# ecg_module_v2_0_1_jan2024.net
KiCad netlist of a schematic drawn in EAGLE
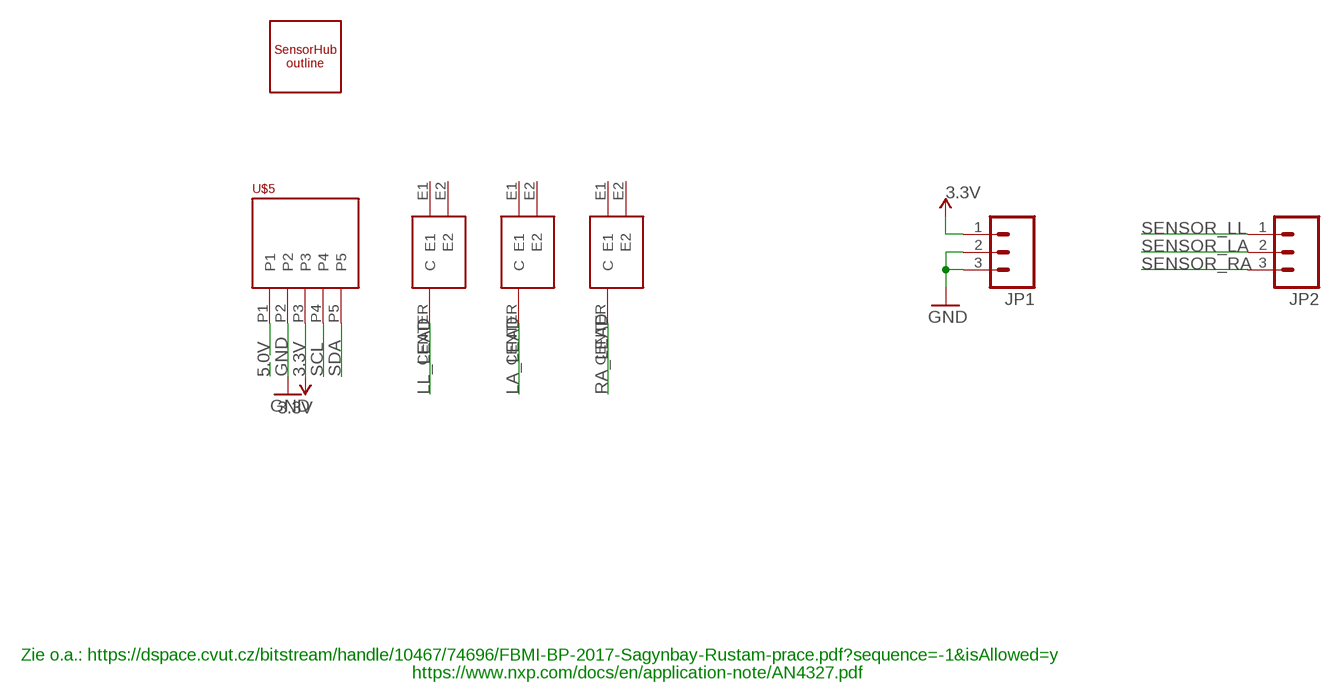
[diagram p0: schematic, sheet 1]
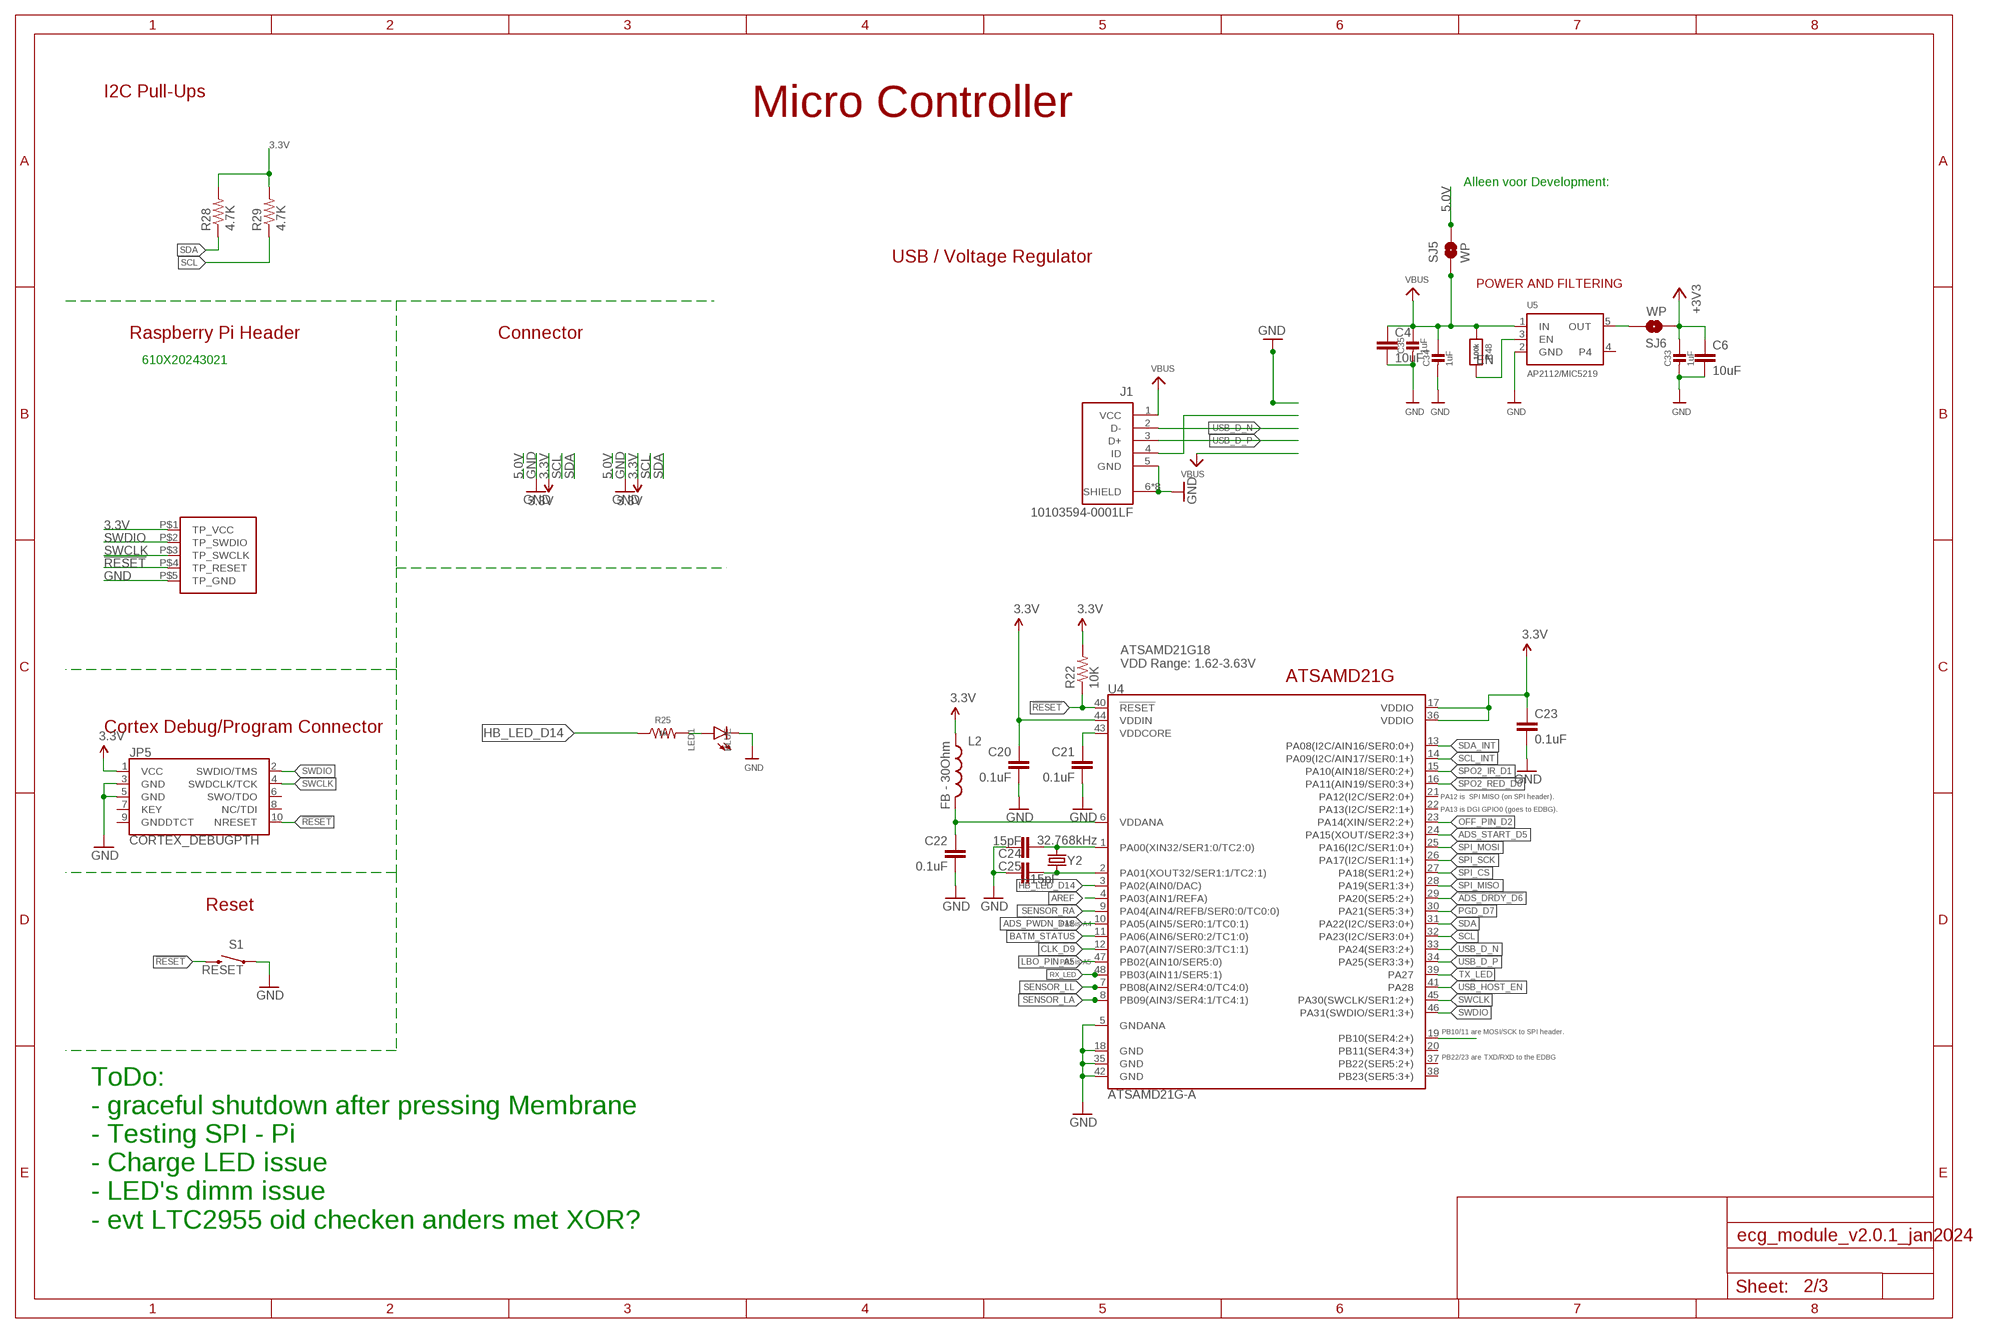
[diagram p1: schematic, sheet 2]
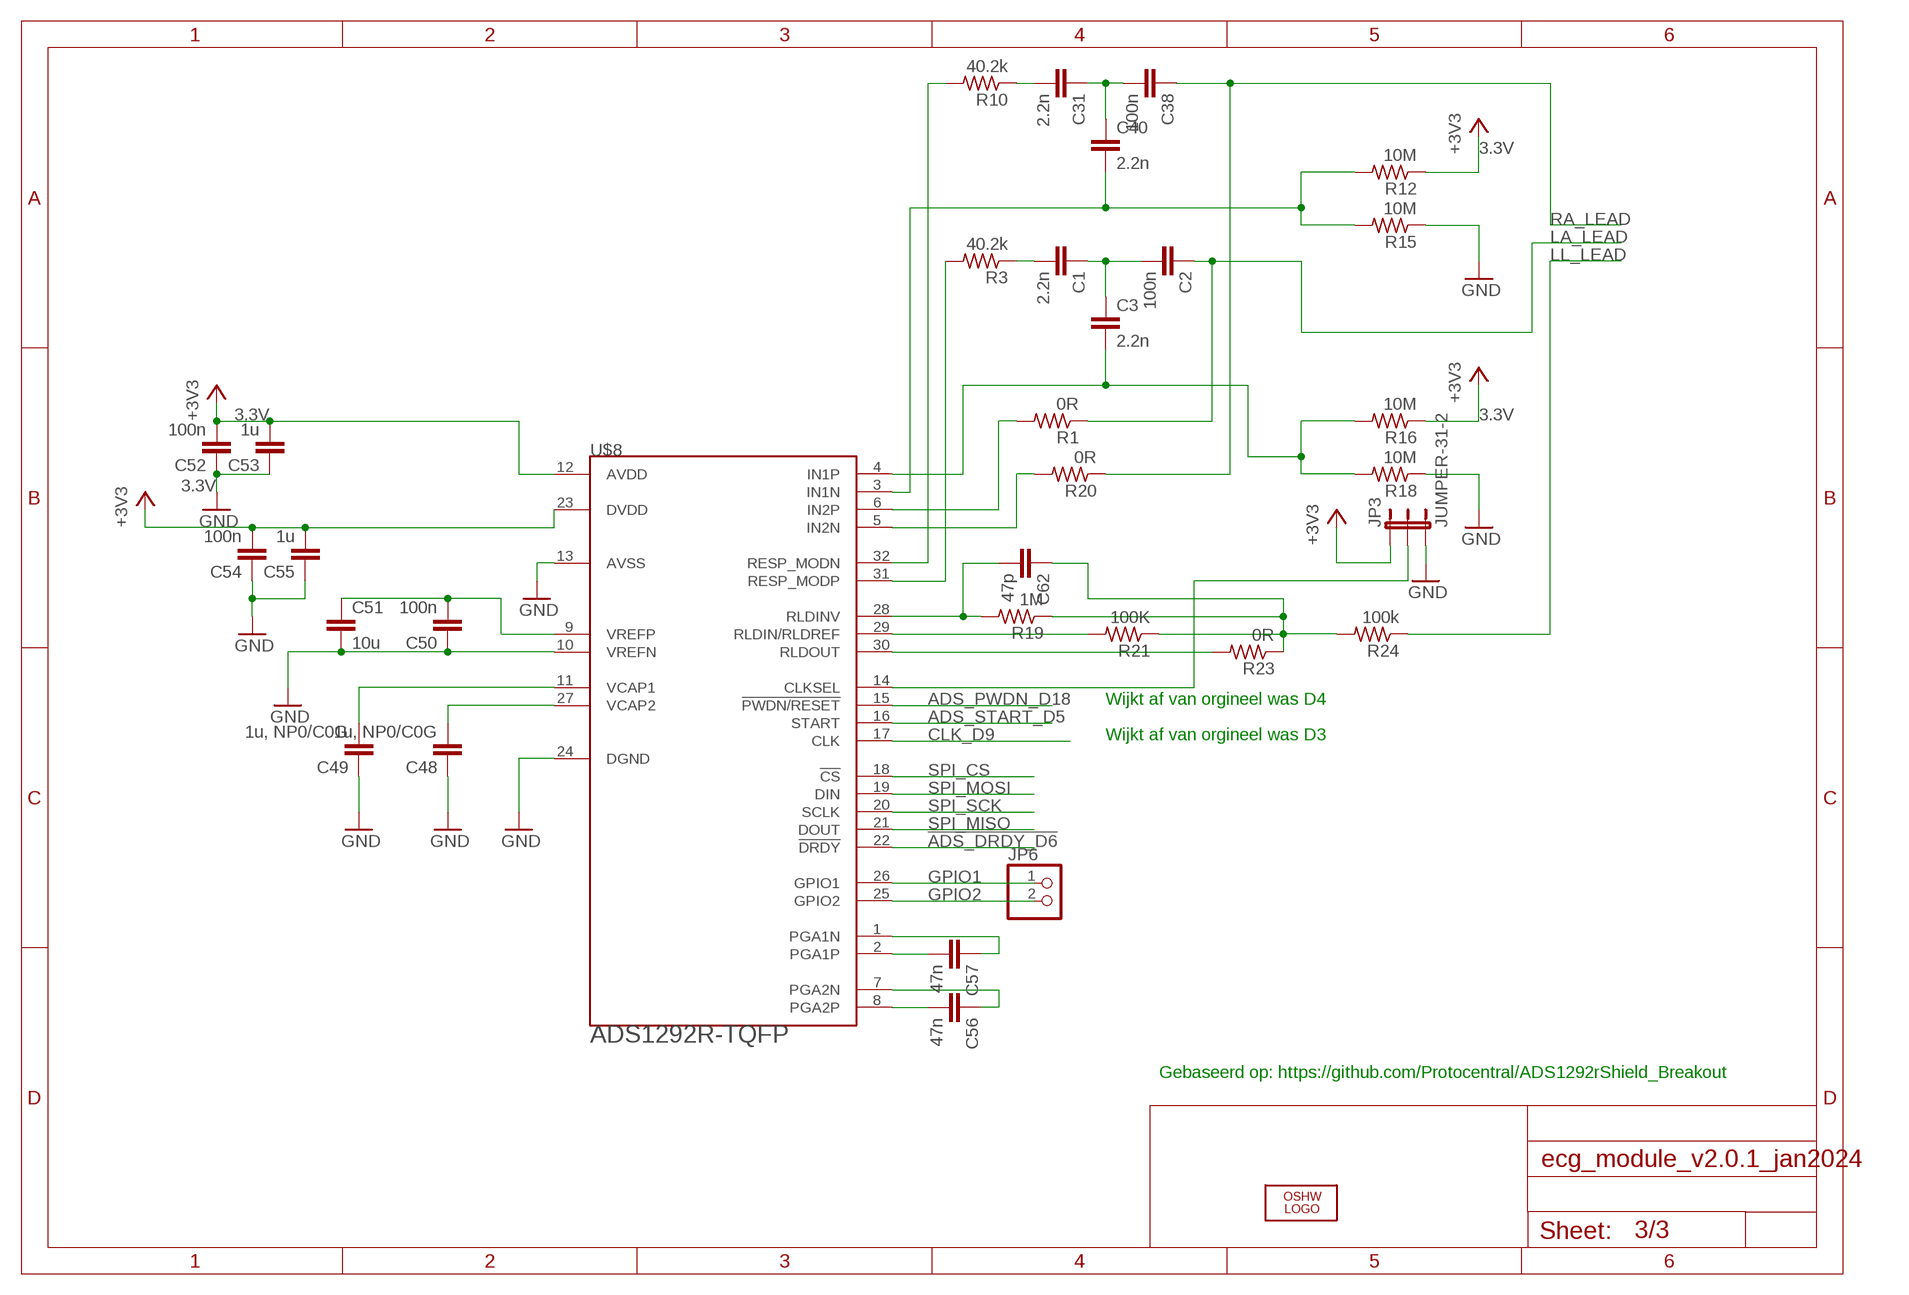
[diagram p2: schematic, sheet 3]

(export (version "E")
  (design (tool "Eeschema 10.0.6"))
  (components
    (comp (ref "C1")
      (value "2.2n")
      (footprint "eagle-import:C0402")
      (libsource (lib "eagle-import") (part "C-EUC0402"))
    )
    (comp (ref "C2")
      (value "100n")
      (footprint "eagle-import:C0402")
      (libsource (lib "eagle-import") (part "C-EUC0402"))
    )
    (comp (ref "C3")
      (value "2.2n")
      (footprint "eagle-import:C0402")
      (libsource (lib "eagle-import") (part "C-EUC0402"))
    )
    (comp (ref "C31")
      (value "2.2n")
      (footprint "eagle-import:C0402")
      (libsource (lib "eagle-import") (part "C-EUC0402"))
    )
    (comp (ref "C38")
      (value "100n")
      (footprint "eagle-import:C0402")
      (libsource (lib "eagle-import") (part "C-EUC0402"))
    )
    (comp (ref "C40")
      (value "2.2n")
      (footprint "eagle-import:C0402")
      (libsource (lib "eagle-import") (part "C-EUC0402"))
    )
    (comp (ref "C48")
      (value "1u, NP0/C0G")
      (footprint "eagle-import:C0402")
      (libsource (lib "eagle-import") (part "C-EUC0402"))
    )
    (comp (ref "C49")
      (value "1u, NP0/C0G")
      (footprint "eagle-import:C0402")
      (libsource (lib "eagle-import") (part "C-EUC0402"))
    )
    (comp (ref "C50")
      (value "100n")
      (footprint "eagle-import:C0402")
      (libsource (lib "eagle-import") (part "C-EUC0402"))
    )
    (comp (ref "C51")
      (value "10u")
      (footprint "eagle-import:C0603")
      (libsource (lib "eagle-import") (part "resistor_348_C-EUC0603"))
    )
    (comp (ref "C52")
      (value "100n")
      (footprint "eagle-import:C0402")
      (libsource (lib "eagle-import") (part "C-EUC0402"))
    )
    (comp (ref "C53")
      (value "1u")
      (footprint "eagle-import:C0402")
      (libsource (lib "eagle-import") (part "C-EUC0402"))
    )
    (comp (ref "C54")
      (value "100n")
      (footprint "eagle-import:C0402")
      (libsource (lib "eagle-import") (part "C-EUC0402"))
    )
    (comp (ref "C55")
      (value "1u")
      (footprint "eagle-import:C0402")
      (libsource (lib "eagle-import") (part "C-EUC0402"))
    )
    (comp (ref "C56")
      (value "47n")
      (footprint "eagle-import:C0402")
      (libsource (lib "eagle-import") (part "C-EUC0402"))
    )
    (comp (ref "C57")
      (value "47n")
      (footprint "eagle-import:C0402")
      (libsource (lib "eagle-import") (part "C-EUC0402"))
    )
    (comp (ref "C62")
      (value "47p")
      (footprint "eagle-import:C0402")
      (libsource (lib "eagle-import") (part "C-EUC0402"))
    )
    (comp (ref "JP3")
      (value "JUMPER-31-2")
      (footprint "eagle-import:SJ_3_PASTE1&2")
      (libsource (lib "eagle-import") (part "JUMPER-31-2"))
    )
    (comp (ref "JP6")
      (value "PINHD-1X2")
      (footprint "eagle-import:1X02")
      (libsource (lib "eagle-import") (part "PINHD-1X2"))
    )
    (comp (ref "LOGO1")
      (value "OSHW_LOGO_FILLX0100-NT")
      (footprint "eagle-import:OSHW_FILLX100_NOTEXT")
      (libsource (lib "eagle-import") (part "OSHW_LOGO_FILLX0100-NT"))
    )
    (comp (ref "R1")
      (value "0R")
      (footprint "eagle-import:R0402")
      (libsource (lib "eagle-import") (part "R-US_R0402"))
    )
    (comp (ref "R3")
      (value "40.2k")
      (footprint "eagle-import:R0402")
      (libsource (lib "eagle-import") (part "R-US_R0402"))
    )
    (comp (ref "R10")
      (value "40.2k")
      (footprint "eagle-import:R0402")
      (libsource (lib "eagle-import") (part "R-US_R0402"))
    )
    (comp (ref "R12")
      (value "10M")
      (footprint "eagle-import:R0402")
      (libsource (lib "eagle-import") (part "R-US_R0402"))
    )
    (comp (ref "R15")
      (value "10M")
      (footprint "eagle-import:R0402")
      (libsource (lib "eagle-import") (part "R-US_R0402"))
    )
    (comp (ref "R16")
      (value "10M")
      (footprint "eagle-import:R0402")
      (libsource (lib "eagle-import") (part "R-US_R0402"))
    )
    (comp (ref "R18")
      (value "10M")
      (footprint "eagle-import:R0402")
      (libsource (lib "eagle-import") (part "R-US_R0402"))
    )
    (comp (ref "R19")
      (value "1M")
      (footprint "eagle-import:R0402")
      (libsource (lib "eagle-import") (part "R-US_R0402"))
    )
    (comp (ref "R20")
      (value "0R")
      (footprint "eagle-import:R0402")
      (libsource (lib "eagle-import") (part "R-US_R0402"))
    )
    (comp (ref "R21")
      (value "100K")
      (footprint "eagle-import:R0402")
      (libsource (lib "eagle-import") (part "R-US_R0402"))
    )
    (comp (ref "R23")
      (value "0R")
      (footprint "eagle-import:R0402")
      (libsource (lib "eagle-import") (part "R-US_R0402"))
    )
    (comp (ref "R24")
      (value "100k")
      (footprint "eagle-import:R0402")
      (libsource (lib "eagle-import") (part "R-US_R0402"))
    )
    (comp (ref "U$8")
      (value "ADS1292R-TQFP")
      (footprint "eagle-import:SQFP-S-5X5-32")
      (libsource (lib "eagle-import") (part "ADS1292R-TQFP"))
    )
    (comp (ref "C4")
      (value "10uF")
      (footprint "eagle-import:0603")
      (libsource (lib "eagle-import") (part "10UF-0603-6.3V-20%"))
    )
    (comp (ref "C6")
      (value "10uF")
      (footprint "eagle-import:0603")
      (libsource (lib "eagle-import") (part "10UF-0603-6.3V-20%"))
    )
    (comp (ref "C20")
      (value "0.1uF")
      (footprint "eagle-import:0402-CAP")
      (libsource (lib "eagle-import") (part "0.1UF-16V(+-10%)(0402)"))
    )
    (comp (ref "C21")
      (value "0.1uF")
      (footprint "eagle-import:0603")
      (libsource (lib "eagle-import") (part "0.1UF-0603-25V-(+80/-20%)"))
    )
    (comp (ref "C22")
      (value "0.1uF")
      (footprint "eagle-import:0402-CAP")
      (libsource (lib "eagle-import") (part "0.1UF-16V(+-10%)(0402)"))
    )
    (comp (ref "C23")
      (value "0.1uF")
      (footprint "eagle-import:0402-CAP")
      (libsource (lib "eagle-import") (part "0.1UF-16V(+-10%)(0402)"))
    )
    (comp (ref "C24")
      (value "15pF")
      (footprint "eagle-import:0402-CAP")
      (libsource (lib "eagle-import") (part "15PF-50V(+-5%)(0402)"))
    )
    (comp (ref "C25")
      (value "15pF")
      (footprint "eagle-import:0402-CAP")
      (libsource (lib "eagle-import") (part "15PF-50V(+-5%)(0402)"))
    )
    (comp (ref "C33")
      (value "1uF")
      (footprint "eagle-import:0603-NO")
      (libsource (lib "eagle-import") (part "CAP_CERAMIC0603_NO"))
    )
    (comp (ref "C34")
      (value "1uF")
      (footprint "eagle-import:0603-NO")
      (libsource (lib "eagle-import") (part "CAP_CERAMIC0603_NO"))
    )
    (comp (ref "C35")
      (value "1uF")
      (footprint "eagle-import:0603-NO")
      (libsource (lib "eagle-import") (part "CAP_CERAMIC0603_NO"))
    )
    (comp (ref "J1")
      (value "10103594-0001LF")
      (footprint "eagle-import:AMPHENOL_10103594-0001LF")
      (fields (field (name "MF") "AMPHENOL ICC / FCI"))
      (libsource (lib "eagle-import") (part "10103594-0001LF"))
    )
    (comp (ref "JP5")
      (value "CORTEX_DEBUGPTH")
      (footprint "eagle-import:2X5-PTH-1.27MM")
      (libsource (lib "eagle-import") (part "CORTEX_DEBUGPTH"))
    )
    (comp (ref "L2")
      (value "FB - 30Ohm")
      (footprint "eagle-import:0603")
      (libsource (lib "eagle-import") (part "INDUCTOR0603"))
    )
    (comp (ref "LED1")
      (value "BLUE")
      (footprint "eagle-import:CHIP-LED0603")
      (libsource (lib "eagle-import") (part "LEDCHIP-LED0603"))
    )
    (comp (ref "R22")
      (value "10K")
      (footprint "eagle-import:0603-RES")
      (libsource (lib "eagle-import") (part "10KOHM-1/10W-1%(0603)0603"))
    )
    (comp (ref "R25")
      (value "1k")
      (footprint "eagle-import:0603")
      (libsource (lib "eagle-import") (part "1KOHM-0603-1/10W-1%"))
    )
    (comp (ref "R28")
      (value "4.7K")
      (footprint "eagle-import:0603-RES")
      (libsource (lib "eagle-import") (part "4.7KOHM-1/10W-1%(0603)"))
    )
    (comp (ref "R29")
      (value "4.7K")
      (footprint "eagle-import:0603-RES")
      (libsource (lib "eagle-import") (part "4.7KOHM-1/10W-1%(0603)"))
    )
    (comp (ref "R48")
      (value "100k")
      (footprint "eagle-import:0603-NO@1")
      (libsource (lib "eagle-import") (part "RESISTOR_0603_NOOUT"))
    )
    (comp (ref "S1")
      (value "RESET")
      (footprint "eagle-import:TACTILE_SWITCH_SMD_4.6X2.8MM")
      (libsource (lib "eagle-import") (part "SWITCH-MOMENTARY-2SMD-4.6X2.8MM"))
    )
    (comp (ref "SJ5")
      (value "WP")
      (footprint "eagle-import:SMT-JUMPER_2_NO_NO-SILK")
      (libsource (lib "eagle-import") (part "JUMPER-SMT_2_NO_NO-SILK"))
    )
    (comp (ref "SJ6")
      (value "WP")
      (footprint "eagle-import:SMT-JUMPER_2_NO_NO-SILK")
      (libsource (lib "eagle-import") (part "JUMPER-SMT_2_NO_NO-SILK"))
    )
    (comp (ref "U$9")
      (value "HUB_TESTPINSHUBS")
      (footprint "eagle-import:TEST_PINS")
      (libsource (lib "eagle-import") (part "HUB_TESTPINSHUBS"))
    )
    (comp (ref "U4")
      (value "ATSAMD21G-A")
      (footprint "eagle-import:TQFP-48")
      (libsource (lib "eagle-import") (part "ATSAMD21G-A"))
    )
    (comp (ref "U5")
      (value "AP2112/MIC5219")
      (footprint "eagle-import:SOT23-5")
      (libsource (lib "eagle-import") (part "VREG_SOT23-5"))
    )
    (comp (ref "Y2")
      (value "32.768kHz")
      (footprint "eagle-import:CRYSTAL-SMD-3.2X1.5MM")
      (libsource (lib "eagle-import") (part "CRYSTAL3.2X1.5MM"))
    )
    (comp (ref "JP1")
      (value "M03PTH")
      (footprint "eagle-import:1X03")
      (libsource (lib "eagle-import") (part "M03PTH"))
    )
    (comp (ref "JP2")
      (value "M03PTH")
      (footprint "eagle-import:1X03")
      (libsource (lib "eagle-import") (part "M03PTH"))
    )
    (comp (ref "U$1")
      (value "DIN_ECG_EEG")
      (footprint "eagle-import:EEG_ECG_DIN")
      (libsource (lib "eagle-import") (part "DIN_ECG_EEG"))
    )
    (comp (ref "U$3")
      (value "DIN_ECG_EEG")
      (footprint "eagle-import:EEG_ECG_DIN")
      (libsource (lib "eagle-import") (part "DIN_ECG_EEG"))
    )
    (comp (ref "U$4")
      (value "DIN_ECG_EEG")
      (footprint "eagle-import:EEG_ECG_DIN")
      (libsource (lib "eagle-import") (part "DIN_ECG_EEG"))
    )
    (comp (ref "U$5")
      (value "PHOENIX_PTSM_M5_TH_I2C++")
      (footprint "eagle-import:PTSM_M5_THRHOLE")
      (libsource (lib "eagle-import") (part "PHOENIX_PTSM_M5_TH_I2C++"))
    )
    (comp (ref "U$12")
      (value "SENSORHUB_PROFILEUSB_LEFT")
      (footprint "eagle-import:SENSORHUB_OUTLINE_USB_NOTCH_LEFT")
      (libsource (lib "eagle-import") (part "SENSORHUB_PROFILEUSB_LEFT"))
    )
  )
  (nets
    (net (code "1") (name "3.3V") (class "Default")
      (node (ref "C20") (pin "1") (pinfunction "1_1") (pintype "passive"))
      (node (ref "C23") (pin "1") (pinfunction "1_1") (pintype "passive"))
      (node (ref "C33") (pin "1") (pinfunction "1_1") (pintype "passive"))
      (node (ref "C52") (pin "2") (pinfunction "2_2") (pintype "passive"))
      (node (ref "C53") (pin "2") (pinfunction "2_2") (pintype "passive"))
      (node (ref "C54") (pin "2") (pinfunction "2_2") (pintype "passive"))
      (node (ref "C55") (pin "2") (pinfunction "2_2") (pintype "passive"))
      (node (ref "C6") (pin "1") (pinfunction "1_1") (pintype "passive"))
      (node (ref "JP1") (pin "1") (pinfunction "1_1") (pintype "passive"))
      (node (ref "JP3") (pin "1") (pinfunction "1_1") (pintype "passive"))
      (node (ref "JP5") (pin "1") (pinfunction "VCC_1") (pintype "bidirectional"))
      (node (ref "L2") (pin "1") (pinfunction "1_1") (pintype "passive"))
      (node (ref "R12") (pin "1") (pinfunction "1_1") (pintype "passive"))
      (node (ref "R16") (pin "1") (pinfunction "1_1") (pintype "passive"))
      (node (ref "R22") (pin "2") (pinfunction "2_2") (pintype "passive"))
      (node (ref "R28") (pin "2") (pinfunction "2_2") (pintype "passive"))
      (node (ref "R29") (pin "2") (pinfunction "2_2") (pintype "passive"))
      (node (ref "SJ6") (pin "1") (pinfunction "1_1") (pintype "passive"))
      (node (ref "U$5") (pin "P3") (pinfunction "P3_P3") (pintype "power_in"))
      (node (ref "U$8") (pin "12") (pinfunction "AVDD_12") (pintype "power_in"))
      (node (ref "U$8") (pin "23") (pinfunction "DVDD_23") (pintype "power_in"))
      (node (ref "U$9") (pin "P$1") (pinfunction "TP_VCC_P$1") (pintype "bidirectional"))
      (node (ref "U4") (pin "17") (pinfunction "VDDIO_17") (pintype "bidirectional"))
      (node (ref "U4") (pin "36") (pinfunction "VDDIO_36") (pintype "bidirectional"))
      (node (ref "U4") (pin "44") (pinfunction "VDDIN_44") (pintype "bidirectional"))
    )
    (net (code "2") (name "5.0V") (class "Default")
      (node (ref "SJ5") (pin "2") (pinfunction "2_2") (pintype "passive"))
      (node (ref "U$5") (pin "P1") (pinfunction "P1_P1") (pintype "power_in"))
    )
    (net (code "3") (name "ADS_PWDN_D18") (class "Default")
      (node (ref "U$8") (pin "15") (pinfunction "~{PWDN/RESET}_15") (pintype "bidirectional"))
      (node (ref "U4") (pin "10") (pinfunction "PA05(AIN5/SER0:1/TC0:1)_10") (pintype "bidirectional"))
    )
    (net (code "4") (name "ADS_START_D5") (class "Default")
      (node (ref "U$8") (pin "16") (pinfunction "START_16") (pintype "bidirectional"))
      (node (ref "U4") (pin "24") (pinfunction "PA15(XOUT/SER2:3+)_24") (pintype "bidirectional"))
    )
    (net (code "5") (name "AREF") (class "Default")
      (node (ref "U4") (pin "4") (pinfunction "PA03(AIN1/REFA)_4") (pintype "bidirectional"))
    )
    (net (code "6") (name "BATM_STATUS") (class "Default")
      (node (ref "U4") (pin "11") (pinfunction "PA06(AIN6/SER0:2/TC1:0)_11") (pintype "bidirectional"))
    )
    (net (code "7") (name "CLK_D9") (class "Default")
      (node (ref "U$8") (pin "17") (pinfunction "CLK_17") (pintype "bidirectional"))
      (node (ref "U4") (pin "12") (pinfunction "PA07(AIN7/SER0:3/TC1:1)_12") (pintype "bidirectional"))
    )
    (net (code "8") (name "EN") (class "Default")
      (node (ref "R48") (pin "2") (pinfunction "2_2") (pintype "passive"))
      (node (ref "U5") (pin "3") (pinfunction "EN_3") (pintype "input"))
    )
    (net (code "9") (name "GND") (class "Default")
      (node (ref "C20") (pin "2") (pinfunction "2_2") (pintype "passive"))
      (node (ref "C21") (pin "2") (pinfunction "2_2") (pintype "passive"))
      (node (ref "C22") (pin "2") (pinfunction "2_2") (pintype "passive"))
      (node (ref "C23") (pin "2") (pinfunction "2_2") (pintype "passive"))
      (node (ref "C24") (pin "1") (pinfunction "1_1") (pintype "passive"))
      (node (ref "C25") (pin "2") (pinfunction "2_2") (pintype "passive"))
      (node (ref "C33") (pin "2") (pinfunction "2_2") (pintype "passive"))
      (node (ref "C34") (pin "2") (pinfunction "2_2") (pintype "passive"))
      (node (ref "C35") (pin "2") (pinfunction "2_2") (pintype "passive"))
      (node (ref "C4") (pin "2") (pinfunction "2_2") (pintype "passive"))
      (node (ref "C48") (pin "1") (pinfunction "1_1") (pintype "passive"))
      (node (ref "C49") (pin "1") (pinfunction "1_1") (pintype "passive"))
      (node (ref "C50") (pin "1") (pinfunction "1_1") (pintype "passive"))
      (node (ref "C51") (pin "2") (pinfunction "2_2") (pintype "passive"))
      (node (ref "C52") (pin "1") (pinfunction "1_1") (pintype "passive"))
      (node (ref "C53") (pin "1") (pinfunction "1_1") (pintype "passive"))
      (node (ref "C54") (pin "1") (pinfunction "1_1") (pintype "passive"))
      (node (ref "C55") (pin "1") (pinfunction "1_1") (pintype "passive"))
      (node (ref "C6") (pin "2") (pinfunction "2_2") (pintype "passive"))
      (node (ref "J1") (pin "10") (pinfunction "SHIELD_10") (pintype "passive"))
      (node (ref "J1") (pin "11") (pinfunction "SHIELD_11") (pintype "passive"))
      (node (ref "J1") (pin "5") (pinfunction "GND_5") (pintype "power_in"))
      (node (ref "J1") (pin "6") (pinfunction "SHIELD_6") (pintype "passive"))
      (node (ref "J1") (pin "7") (pinfunction "SHIELD_7") (pintype "passive"))
      (node (ref "J1") (pin "8") (pinfunction "SHIELD_8") (pintype "passive"))
      (node (ref "J1") (pin "9") (pinfunction "SHIELD_9") (pintype "passive"))
      (node (ref "J1") (pin "S1") (pinfunction "SHIELD_S1") (pintype "passive"))
      (node (ref "J1") (pin "S2") (pinfunction "SHIELD_S2") (pintype "passive"))
      (node (ref "JP1") (pin "2") (pinfunction "2_2") (pintype "passive"))
      (node (ref "JP1") (pin "3") (pinfunction "3_3") (pintype "passive"))
      (node (ref "JP3") (pin "3") (pinfunction "3_3") (pintype "passive"))
      (node (ref "JP5") (pin "3") (pinfunction "GND_3") (pintype "bidirectional"))
      (node (ref "JP5") (pin "5") (pinfunction "GND_5") (pintype "bidirectional"))
      (node (ref "LED1") (pin "C") (pinfunction "C_C") (pintype "passive"))
      (node (ref "R15") (pin "1") (pinfunction "1_1") (pintype "passive"))
      (node (ref "R18") (pin "1") (pinfunction "1_1") (pintype "passive"))
      (node (ref "S1") (pin "1") (pinfunction "1_1") (pintype "passive"))
      (node (ref "S1") (pin "2") (pinfunction "1_2") (pintype "passive"))
      (node (ref "U$5") (pin "P2") (pinfunction "P2_P2") (pintype "power_in"))
      (node (ref "U$8") (pin "10") (pinfunction "VREFN_10") (pintype "bidirectional"))
      (node (ref "U$8") (pin "13") (pinfunction "AVSS_13") (pintype "bidirectional"))
      (node (ref "U$8") (pin "24") (pinfunction "DGND_24") (pintype "bidirectional"))
      (node (ref "U$9") (pin "P$5") (pinfunction "TP_GND_P$5") (pintype "bidirectional"))
      (node (ref "U4") (pin "18") (pinfunction "GND_18") (pintype "bidirectional"))
      (node (ref "U4") (pin "35") (pinfunction "GND_35") (pintype "bidirectional"))
      (node (ref "U4") (pin "42") (pinfunction "GND_42") (pintype "bidirectional"))
      (node (ref "U4") (pin "5") (pinfunction "GNDANA_5") (pintype "bidirectional"))
      (node (ref "U5") (pin "2") (pinfunction "GND_2") (pintype "power_in"))
    )
    (net (code "10") (name "GPIO1") (class "Default")
      (node (ref "JP6") (pin "1") (pinfunction "1_1") (pintype "passive"))
      (node (ref "U$8") (pin "26") (pinfunction "GPIO1_26") (pintype "bidirectional"))
    )
    (net (code "11") (name "GPIO2") (class "Default")
      (node (ref "JP6") (pin "2") (pinfunction "2_2") (pintype "passive"))
      (node (ref "U$8") (pin "25") (pinfunction "GPIO2_25") (pintype "bidirectional"))
    )
    (net (code "12") (name "HB_LED_D14") (class "Default")
      (node (ref "R25") (pin "1") (pinfunction "1_1") (pintype "passive"))
      (node (ref "U4") (pin "3") (pinfunction "PA02(AIN0/DAC)_3") (pintype "bidirectional"))
    )
    (net (code "13") (name "LA_LEAD") (class "Default")
      (node (ref "C2") (pin "1") (pinfunction "1_1") (pintype "passive"))
      (node (ref "R1") (pin "1") (pinfunction "1_1") (pintype "passive"))
      (node (ref "U$3") (pin "CENTER") (pinfunction "C_CENTER") (pintype "bidirectional"))
    )
    (net (code "14") (name "LBO_PIN_A5") (class "Default")
      (node (ref "U4") (pin "47") (pinfunction "PB02(AIN10/SER5:0)_47") (pintype "bidirectional"))
    )
    (net (code "15") (name "LL_LEAD") (class "Default")
      (node (ref "R24") (pin "1") (pinfunction "1_1") (pintype "passive"))
      (node (ref "U$1") (pin "CENTER") (pinfunction "C_CENTER") (pintype "bidirectional"))
    )
    (net (code "16") (name "Net-(C1-Pad1)") (class "Default")
      (node (ref "C1") (pin "1") (pinfunction "1_1") (pintype "passive"))
      (node (ref "C2") (pin "2") (pinfunction "2_2") (pintype "passive"))
      (node (ref "C3") (pin "1") (pinfunction "1_1") (pintype "passive"))
    )
    (net (code "17") (name "Net-(C1-Pad2)") (class "Default")
      (node (ref "C1") (pin "2") (pinfunction "2_2") (pintype "passive"))
      (node (ref "R3") (pin "1") (pinfunction "1_1") (pintype "passive"))
    )
    (net (code "18") (name "Net-(C31-Pad1)") (class "Default")
      (node (ref "C31") (pin "1") (pinfunction "1_1") (pintype "passive"))
      (node (ref "C38") (pin "2") (pinfunction "2_2") (pintype "passive"))
      (node (ref "C40") (pin "1") (pinfunction "1_1") (pintype "passive"))
    )
    (net (code "19") (name "Net-(C31-Pad2)") (class "Default")
      (node (ref "C31") (pin "2") (pinfunction "2_2") (pintype "passive"))
      (node (ref "R10") (pin "1") (pinfunction "1_1") (pintype "passive"))
    )
    (net (code "20") (name "Net-(C62-Pad1)") (class "Default")
      (node (ref "C62") (pin "1") (pinfunction "1_1") (pintype "passive"))
      (node (ref "R19") (pin "1") (pinfunction "1_1") (pintype "passive"))
      (node (ref "R21") (pin "1") (pinfunction "1_1") (pintype "passive"))
      (node (ref "R23") (pin "1") (pinfunction "1_1") (pintype "passive"))
      (node (ref "R24") (pin "2") (pinfunction "2_2") (pintype "passive"))
    )
    (net (code "21") (name "Net-(LED1-PadA)") (class "Default")
      (node (ref "LED1") (pin "A") (pinfunction "A_A") (pintype "passive"))
      (node (ref "R25") (pin "2") (pinfunction "2_2") (pintype "passive"))
    )
    (net (code "22") (name "Net-(U$8-CLKSEL)") (class "Default")
      (node (ref "JP3") (pin "2") (pinfunction "2_2") (pintype "passive"))
      (node (ref "U$8") (pin "14") (pinfunction "CLKSEL_14") (pintype "bidirectional"))
    )
    (net (code "23") (name "Net-(U$8-IN1N)") (class "Default")
      (node (ref "C40") (pin "2") (pinfunction "2_2") (pintype "passive"))
      (node (ref "R12") (pin "2") (pinfunction "2_2") (pintype "passive"))
      (node (ref "R15") (pin "2") (pinfunction "2_2") (pintype "passive"))
      (node (ref "U$8") (pin "3") (pinfunction "IN1N_3") (pintype "input"))
    )
    (net (code "24") (name "Net-(U$8-IN1P)") (class "Default")
      (node (ref "C3") (pin "2") (pinfunction "2_2") (pintype "passive"))
      (node (ref "R16") (pin "2") (pinfunction "2_2") (pintype "passive"))
      (node (ref "R18") (pin "2") (pinfunction "2_2") (pintype "passive"))
      (node (ref "U$8") (pin "4") (pinfunction "IN1P_4") (pintype "input"))
    )
    (net (code "25") (name "Net-(U$8-IN2N)") (class "Default")
      (node (ref "R20") (pin "2") (pinfunction "2_2") (pintype "passive"))
      (node (ref "U$8") (pin "5") (pinfunction "IN2N_5") (pintype "input"))
    )
    (net (code "26") (name "Net-(U$8-IN2P)") (class "Default")
      (node (ref "R1") (pin "2") (pinfunction "2_2") (pintype "passive"))
      (node (ref "U$8") (pin "6") (pinfunction "IN2P_6") (pintype "input"))
    )
    (net (code "27") (name "Net-(U$8-PGA1N)") (class "Default")
      (node (ref "C57") (pin "1") (pinfunction "1_1") (pintype "passive"))
      (node (ref "U$8") (pin "1") (pinfunction "PGA1N_1") (pintype "bidirectional"))
    )
    (net (code "28") (name "Net-(U$8-PGA1P)") (class "Default")
      (node (ref "C57") (pin "2") (pinfunction "2_2") (pintype "passive"))
      (node (ref "U$8") (pin "2") (pinfunction "PGA1P_2") (pintype "bidirectional"))
    )
    (net (code "29") (name "Net-(U$8-PGA2N)") (class "Default")
      (node (ref "C56") (pin "1") (pinfunction "1_1") (pintype "passive"))
      (node (ref "U$8") (pin "7") (pinfunction "PGA2N_7") (pintype "bidirectional"))
    )
    (net (code "30") (name "Net-(U$8-PGA2P)") (class "Default")
      (node (ref "C56") (pin "2") (pinfunction "2_2") (pintype "passive"))
      (node (ref "U$8") (pin "8") (pinfunction "PGA2P_8") (pintype "bidirectional"))
    )
    (net (code "31") (name "Net-(U$8-RESP_MODN)") (class "Default")
      (node (ref "R10") (pin "2") (pinfunction "2_2") (pintype "passive"))
      (node (ref "U$8") (pin "32") (pinfunction "RESP_MODN_32") (pintype "bidirectional"))
    )
    (net (code "32") (name "Net-(U$8-RESP_MODP)") (class "Default")
      (node (ref "R3") (pin "2") (pinfunction "2_2") (pintype "passive"))
      (node (ref "U$8") (pin "31") (pinfunction "RESP_MODP_31") (pintype "bidirectional"))
    )
    (net (code "33") (name "Net-(U$8-RLDINV)") (class "Default")
      (node (ref "C62") (pin "2") (pinfunction "2_2") (pintype "passive"))
      (node (ref "R19") (pin "2") (pinfunction "2_2") (pintype "passive"))
      (node (ref "U$8") (pin "28") (pinfunction "RLDINV_28") (pintype "bidirectional"))
    )
    (net (code "34") (name "Net-(U$8-RLDIN{slash}RLDREF)") (class "Default")
      (node (ref "R21") (pin "2") (pinfunction "2_2") (pintype "passive"))
      (node (ref "U$8") (pin "29") (pinfunction "RLDIN/RLDREF_29") (pintype "bidirectional"))
    )
    (net (code "35") (name "Net-(U$8-RLDOUT)") (class "Default")
      (node (ref "R23") (pin "2") (pinfunction "2_2") (pintype "passive"))
      (node (ref "U$8") (pin "30") (pinfunction "RLDOUT_30") (pintype "bidirectional"))
    )
    (net (code "36") (name "Net-(U$8-VCAP1)") (class "Default")
      (node (ref "C49") (pin "2") (pinfunction "2_2") (pintype "passive"))
      (node (ref "U$8") (pin "11") (pinfunction "VCAP1_11") (pintype "bidirectional"))
    )
    (net (code "37") (name "Net-(U$8-VCAP2)") (class "Default")
      (node (ref "C48") (pin "2") (pinfunction "2_2") (pintype "passive"))
      (node (ref "U$8") (pin "27") (pinfunction "VCAP2_27") (pintype "bidirectional"))
    )
    (net (code "38") (name "Net-(U$8-VREFP)") (class "Default")
      (node (ref "C50") (pin "2") (pinfunction "2_2") (pintype "passive"))
      (node (ref "C51") (pin "1") (pinfunction "1_1") (pintype "passive"))
      (node (ref "U$8") (pin "9") (pinfunction "VREFP_9") (pintype "bidirectional"))
    )
    (net (code "39") (name "Net-(U4-PA00(XIN32{slash}SER1:0{slash}TC2:0))") (class "Default")
      (node (ref "C24") (pin "2") (pinfunction "2_2") (pintype "passive"))
      (node (ref "U4") (pin "1") (pinfunction "PA00(XIN32/SER1:0/TC2:0)_1") (pintype "bidirectional"))
      (node (ref "Y2") (pin "P$2") (pinfunction "2_P$2") (pintype "passive"))
    )
    (net (code "40") (name "Net-(U4-PA01(XOUT32{slash}SER1:1{slash}TC2:1))") (class "Default")
      (node (ref "C25") (pin "1") (pinfunction "1_1") (pintype "passive"))
      (node (ref "U4") (pin "2") (pinfunction "PA01(XOUT32/SER1:1/TC2:1)_2") (pintype "bidirectional"))
      (node (ref "Y2") (pin "P$1") (pinfunction "1_P$1") (pintype "passive"))
    )
    (net (code "41") (name "Net-(U4-VDDANA)") (class "Default")
      (node (ref "C22") (pin "1") (pinfunction "1_1") (pintype "passive"))
      (node (ref "L2") (pin "2") (pinfunction "2_2") (pintype "passive"))
      (node (ref "U4") (pin "6") (pinfunction "VDDANA_6") (pintype "bidirectional"))
    )
    (net (code "42") (name "Net-(U4-VDDCORE)") (class "Default")
      (node (ref "C21") (pin "1") (pinfunction "1_1") (pintype "passive"))
      (node (ref "U4") (pin "43") (pinfunction "VDDCORE_43") (pintype "bidirectional"))
    )
    (net (code "43") (name "Net-(U5-OUT)") (class "Default")
      (node (ref "SJ6") (pin "2") (pinfunction "2_2") (pintype "passive"))
      (node (ref "U5") (pin "5") (pinfunction "OUT_5") (pintype "power_in"))
    )
    (net (code "44") (name "OFF_PIN_D2") (class "Default")
      (node (ref "U4") (pin "23") (pinfunction "PA14(XIN/SER2:2+)_23") (pintype "bidirectional"))
    )
    (net (code "45") (name "PGD_D7") (class "Default")
      (node (ref "U4") (pin "30") (pinfunction "PA21(SER5:3+)_30") (pintype "bidirectional"))
    )
    (net (code "46") (name "RA_LEAD") (class "Default")
      (node (ref "C38") (pin "1") (pinfunction "1_1") (pintype "passive"))
      (node (ref "R20") (pin "1") (pinfunction "1_1") (pintype "passive"))
      (node (ref "U$4") (pin "CENTER") (pinfunction "C_CENTER") (pintype "bidirectional"))
    )
    (net (code "47") (name "RX_LED") (class "Default")
      (node (ref "U4") (pin "48") (pinfunction "PB03(AIN11/SER5:1)_48") (pintype "bidirectional"))
    )
    (net (code "48") (name "SCL") (class "Default")
      (node (ref "R29") (pin "1") (pinfunction "1_1") (pintype "passive"))
      (node (ref "U$5") (pin "P4") (pinfunction "P4_P4") (pintype "bidirectional"))
      (node (ref "U4") (pin "32") (pinfunction "PA23(I2C/SER3:0+)_32") (pintype "bidirectional"))
    )
    (net (code "49") (name "SCL_INT") (class "Default")
      (node (ref "U4") (pin "14") (pinfunction "PA09(I2C/AIN17/SER0:1+)_14") (pintype "bidirectional"))
    )
    (net (code "50") (name "SDA") (class "Default")
      (node (ref "R28") (pin "1") (pinfunction "1_1") (pintype "passive"))
      (node (ref "U$5") (pin "P5") (pinfunction "P5_P5") (pintype "bidirectional"))
      (node (ref "U4") (pin "31") (pinfunction "PA22(I2C/SER3:0+)_31") (pintype "bidirectional"))
    )
    (net (code "51") (name "SDA_INT") (class "Default")
      (node (ref "U4") (pin "13") (pinfunction "PA08(I2C/AIN16/SER0:0+)_13") (pintype "bidirectional"))
    )
    (net (code "52") (name "SENSOR_LA") (class "Default")
      (node (ref "JP2") (pin "2") (pinfunction "2_2") (pintype "passive"))
      (node (ref "U4") (pin "8") (pinfunction "PB09(AIN3/SER4:1/TC4:1)_8") (pintype "bidirectional"))
    )
    (net (code "53") (name "SENSOR_LL") (class "Default")
      (node (ref "JP2") (pin "1") (pinfunction "1_1") (pintype "passive"))
      (node (ref "U4") (pin "7") (pinfunction "PB08(AIN2/SER4:0/TC4:0)_7") (pintype "bidirectional"))
    )
    (net (code "54") (name "SENSOR_RA") (class "Default")
      (node (ref "JP2") (pin "3") (pinfunction "3_3") (pintype "passive"))
      (node (ref "U4") (pin "9") (pinfunction "PA04(AIN4/REFB/SER0:0/TC0:0)_9") (pintype "bidirectional"))
    )
    (net (code "55") (name "SPI_CS") (class "Default")
      (node (ref "U$8") (pin "18") (pinfunction "~{CS}_18") (pintype "bidirectional"))
      (node (ref "U4") (pin "27") (pinfunction "PA18(SER1:2+)_27") (pintype "bidirectional"))
    )
    (net (code "56") (name "SPI_MISO") (class "Default")
      (node (ref "U$8") (pin "21") (pinfunction "DOUT_21") (pintype "bidirectional"))
      (node (ref "U4") (pin "28") (pinfunction "PA19(SER1:3+)_28") (pintype "bidirectional"))
    )
    (net (code "57") (name "SPI_MOSI") (class "Default")
      (node (ref "U$8") (pin "19") (pinfunction "DIN_19") (pintype "bidirectional"))
      (node (ref "U4") (pin "25") (pinfunction "PA16(I2C/SER1:0+)_25") (pintype "bidirectional"))
    )
    (net (code "58") (name "SPI_SCK") (class "Default")
      (node (ref "U$8") (pin "20") (pinfunction "SCLK_20") (pintype "bidirectional"))
      (node (ref "U4") (pin "26") (pinfunction "PA17(I2C/SER1:1+)_26") (pintype "bidirectional"))
    )
    (net (code "59") (name "SPO2_IR_D1") (class "Default")
      (node (ref "U4") (pin "15") (pinfunction "PA10(AIN18/SER0:2+)_15") (pintype "bidirectional"))
    )
    (net (code "60") (name "SPO2_RED_D0") (class "Default")
      (node (ref "U4") (pin "16") (pinfunction "PA11(AIN19/SER0:3+)_16") (pintype "bidirectional"))
    )
    (net (code "61") (name "SWCLK") (class "Default")
      (node (ref "JP5") (pin "4") (pinfunction "SWDCLK/TCK_4") (pintype "bidirectional"))
      (node (ref "U$9") (pin "P$3") (pinfunction "TP_SWCLK_P$3") (pintype "bidirectional"))
      (node (ref "U4") (pin "45") (pinfunction "PA30(SWCLK/SER1:2+)_45") (pintype "bidirectional"))
    )
    (net (code "62") (name "SWDIO") (class "Default")
      (node (ref "JP5") (pin "2") (pinfunction "SWDIO/TMS_2") (pintype "bidirectional"))
      (node (ref "U$9") (pin "P$2") (pinfunction "TP_SWDIO_P$2") (pintype "bidirectional"))
      (node (ref "U4") (pin "46") (pinfunction "PA31(SWDIO/SER1:3+)_46") (pintype "bidirectional"))
    )
    (net (code "63") (name "TX_LED") (class "Default")
      (node (ref "U4") (pin "39") (pinfunction "PA27_39") (pintype "bidirectional"))
    )
    (net (code "64") (name "USB_D_N") (class "Default")
      (node (ref "J1") (pin "2") (pinfunction "D-_2") (pintype "bidirectional"))
      (node (ref "U4") (pin "33") (pinfunction "PA24(SER3:2+)_33") (pintype "bidirectional"))
    )
    (net (code "65") (name "USB_D_P") (class "Default")
      (node (ref "J1") (pin "3") (pinfunction "D+_3") (pintype "bidirectional"))
      (node (ref "U4") (pin "34") (pinfunction "PA25(SER3:3+)_34") (pintype "bidirectional"))
    )
    (net (code "66") (name "USB_HOST_EN") (class "Default")
      (node (ref "U4") (pin "41") (pinfunction "PA28_41") (pintype "bidirectional"))
    )
    (net (code "67") (name "VBUS") (class "Default")
      (node (ref "C34") (pin "1") (pinfunction "1_1") (pintype "passive"))
      (node (ref "C35") (pin "1") (pinfunction "1_1") (pintype "passive"))
      (node (ref "C4") (pin "1") (pinfunction "1_1") (pintype "passive"))
      (node (ref "J1") (pin "1") (pinfunction "VCC_1") (pintype "power_in"))
      (node (ref "R48") (pin "1") (pinfunction "1_1") (pintype "passive"))
      (node (ref "SJ5") (pin "1") (pinfunction "1_1") (pintype "passive"))
      (node (ref "U5") (pin "1") (pinfunction "IN_1") (pintype "power_in"))
    )
    (net (code "68") (name "unconnected-(J1-ID-Pad4)") (class "Default")
      (node (ref "J1") (pin "4") (pinfunction "ID_4") (pintype "bidirectional"))
    )
    (net (code "69") (name "unconnected-(JP5-GNDDTCT-Pad9)") (class "Default")
      (node (ref "JP5") (pin "9") (pinfunction "GNDDTCT_9") (pintype "bidirectional"))
    )
    (net (code "70") (name "unconnected-(JP5-KEY-Pad7)") (class "Default")
      (node (ref "JP5") (pin "7") (pinfunction "KEY_7") (pintype "bidirectional"))
    )
    (net (code "71") (name "unconnected-(JP5-NC{slash}TDI-Pad8)") (class "Default")
      (node (ref "JP5") (pin "8") (pinfunction "NC/TDI_8") (pintype "bidirectional"))
    )
    (net (code "72") (name "unconnected-(JP5-SWO{slash}TDO-Pad6)") (class "Default")
      (node (ref "JP5") (pin "6") (pinfunction "SWO/TDO_6") (pintype "bidirectional"))
    )
    (net (code "73") (name "unconnected-(U$1-PadE1)") (class "Default")
      (node (ref "U$1") (pin "E1") (pinfunction "E1_E1") (pintype "bidirectional"))
    )
    (net (code "74") (name "unconnected-(U$1-PadE2)") (class "Default")
      (node (ref "U$1") (pin "E2") (pinfunction "E2_E2") (pintype "bidirectional"))
    )
    (net (code "75") (name "unconnected-(U$3-PadE1)") (class "Default")
      (node (ref "U$3") (pin "E1") (pinfunction "E1_E1") (pintype "bidirectional"))
    )
    (net (code "76") (name "unconnected-(U$3-PadE2)") (class "Default")
      (node (ref "U$3") (pin "E2") (pinfunction "E2_E2") (pintype "bidirectional"))
    )
    (net (code "77") (name "unconnected-(U$4-PadE1)") (class "Default")
      (node (ref "U$4") (pin "E1") (pinfunction "E1_E1") (pintype "bidirectional"))
    )
    (net (code "78") (name "unconnected-(U$4-PadE2)") (class "Default")
      (node (ref "U$4") (pin "E2") (pinfunction "E2_E2") (pintype "bidirectional"))
    )
    (net (code "79") (name "unconnected-(U4-PA12(I2C{slash}SER2:0+)-Pad21)") (class "Default")
      (node (ref "U4") (pin "21") (pinfunction "PA12(I2C/SER2:0+)_21") (pintype "bidirectional"))
    )
    (net (code "80") (name "unconnected-(U4-PA13(I2C{slash}SER2:1+)-Pad22)") (class "Default")
      (node (ref "U4") (pin "22") (pinfunction "PA13(I2C/SER2:1+)_22") (pintype "bidirectional"))
    )
    (net (code "81") (name "unconnected-(U4-PB10(SER4:2+)-Pad19)") (class "Default")
      (node (ref "U4") (pin "19") (pinfunction "PB10(SER4:2+)_19") (pintype "bidirectional"))
    )
    (net (code "82") (name "unconnected-(U4-PB11(SER4:3+)-Pad20)") (class "Default")
      (node (ref "U4") (pin "20") (pinfunction "PB11(SER4:3+)_20") (pintype "bidirectional"))
    )
    (net (code "83") (name "unconnected-(U4-PB22(SER5:2+)-Pad37)") (class "Default")
      (node (ref "U4") (pin "37") (pinfunction "PB22(SER5:2+)_37") (pintype "bidirectional"))
    )
    (net (code "84") (name "unconnected-(U4-PB23(SER5:3+)-Pad38)") (class "Default")
      (node (ref "U4") (pin "38") (pinfunction "PB23(SER5:3+)_38") (pintype "bidirectional"))
    )
    (net (code "85") (name "unconnected-(U5-P4-Pad4)") (class "Default")
      (node (ref "U5") (pin "4") (pinfunction "P4_4") (pintype "bidirectional"))
    )
    (net (code "86") (name "~{ADS_DRDY_D6}") (class "Default")
      (node (ref "U$8") (pin "22") (pinfunction "~{DRDY}_22") (pintype "bidirectional"))
      (node (ref "U4") (pin "29") (pinfunction "PA20(SER5:2+)_29") (pintype "bidirectional"))
    )
    (net (code "87") (name "~{RESET}") (class "Default")
      (node (ref "JP5") (pin "10") (pinfunction "NRESET_10") (pintype "bidirectional"))
      (node (ref "R22") (pin "1") (pinfunction "1_1") (pintype "passive"))
      (node (ref "S1") (pin "3") (pinfunction "2_3") (pintype "passive"))
      (node (ref "S1") (pin "4") (pinfunction "2_4") (pintype "passive"))
      (node (ref "U$9") (pin "P$4") (pinfunction "TP_RESET_P$4") (pintype "bidirectional"))
      (node (ref "U4") (pin "40") (pinfunction "~{RESET}_40") (pintype "bidirectional"))
    )
  )
)
